# cpuofmicrocontroller.net
KiCad netlist of a schematic drawn in Altium Designer
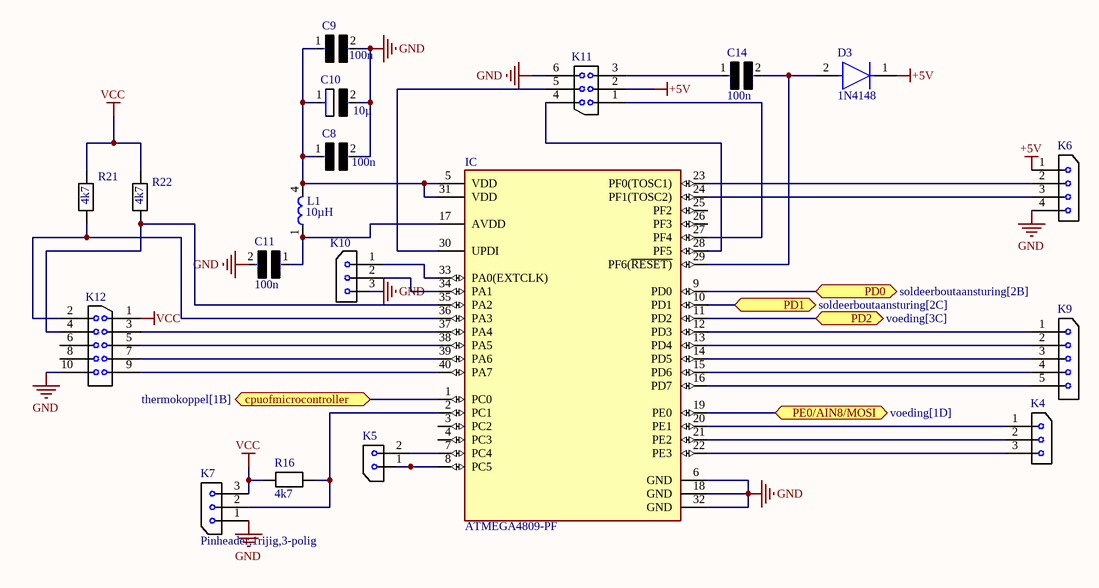
[diagram p0: cpuofmicrocontroller.SchDoc]

(export (version "E")
  (design (tool "Eeschema 10.0.6"))
  (components
    (comp (ref "C8")
      (value "100n")
      (footprint "RESC2013X50X30LL20T20")
      (libsource (lib "Schlib1") (part "capacitor2"))
    )
    (comp (ref "C9")
      (value "100n")
      (footprint "RESC2013X50X30LL20T20")
      (libsource (lib "Schlib1") (part "capacitor2"))
    )
    (comp (ref "C10")
      (value "10µ")
      (footprint "RESC2013X50X30LL20T20")
      (description "CAP CER 0.1UF 10V X5R 0402")
      (fields (field (name "MANUFACTURER") "Kemet") (field (name "TOLERANCE") "0.1"))
      (libsource (lib "Schlib1") (part "Capacitor"))
    )
    (comp (ref "C11")
      (value "100n")
      (footprint "RESC2013X50X30LL20T20")
      (libsource (lib "Schlib1") (part "capacitor2"))
    )
    (comp (ref "C14")
      (value "100n")
      (footprint "RESC2013X50X30LL20T20")
      (libsource (lib "Schlib1") (part "Ceramische Capacitor"))
    )
    (comp (ref "D3")
      (value "1N4148")
      (footprint "FP-017AG-MFG")
      (description "DIODE GEN PURP 100V 200MA DO35/1N4148")
      (fields (field (name "VOLTAGE") "100V"))
      (libsource (lib "Schlib1") (part "1N4148"))
    )
    (comp (ref "IC")
      (value "ATMEGA4809-PF")
      (footprint "FP-C04-016-MFG")
      (description "IC MCU 8BIT 48KB FLASH 40DIP")
      (libsource (lib "Schlib1") (part "aTmega4809-PF"))
    )
    (comp (ref "K4")
      (value "~")
      (footprint "PINHEADER, 1RIJIG,3-POLIG")
      (libsource (lib "Schlib1") (part "Pinheader,1rijig,3-polig"))
    )
    (comp (ref "K5")
      (value "~")
      (footprint "Pinheader,1rijig,2-polig")
      (libsource (lib "Schlib1") (part "Pinheader,1rijig,2-polig"))
    )
    (comp (ref "K6")
      (value "~")
      (footprint "PINHEADER, 1RIJIG,4-POLIG - duplicate")
      (libsource (lib "Schlib1") (part "Pinheader,1rijig,4-polig"))
    )
    (comp (ref "K7")
      (value "Pinheader,1rijig,3-polig")
      (footprint "PINHEADER, 1RIJIG,3-POLIG")
      (libsource (lib "Schlib1") (part "Pinheader,1rijig,3-polig"))
    )
    (comp (ref "K9")
      (value "~")
      (footprint "HDRV5W67P0X254_1X5_1270X241X858P")
      (description "Connector")
      (fields
        (field (name "MANUFACTURER_PART_NUMBER") "68000-105HTLF")
        (field (name "MOUSER PART NUMBER") "649-68000-105HTLF")
      )
      (libsource (lib "Schlib1") (part "5PIN HEADERmale"))
    )
    (comp (ref "K10")
      (value "~")
      (footprint "PINHEADER, 1RIJIG,3-POLIG")
      (libsource (lib "") (part "Pinheader,1rijig,3-polig_1"))
    )
    (comp (ref "K11")
      (value "~")
      (footprint "PINHEADER, 1RIJIG,6-POLIG - duplicate - duplicate")
      (libsource (lib "Schlib1") (part "Pinheader,2rijig,6-polig"))
    )
    (comp (ref "K12")
      (value "Pinheader,2rijig,10-polig")
      (footprint "PINHEADER, 2RIJIG,10-POLIG - duplicate - duplicate - duplicate")
      (libsource (lib "Schlib1") (part "Pinheader,2rijig,10-polig"))
    )
    (comp (ref "L1")
      (value "10µH")
      (footprint "Laird CM2545x171B-10")
      (libsource (lib "Schlib1") (part "spoelL1"))
    )
    (comp (ref "R16")
      (value "4k7")
      (footprint "RESC2013X50X30LL20T20")
      (fields (field (name "MANUFACTURER") "Vishay Dale") (field (name "PART NUMBER") "CRCW08050000Z0EA"))
      (libsource (lib "Schlib1") (part "weerstand"))
    )
    (comp (ref "R21")
      (value "4k7")
      (footprint "RESC2013X50X30LL20T20")
      (fields (field (name "MANUFACTURER") "Vishay Dale") (field (name "PART NUMBER") "CRCW08050000Z0EA"))
      (libsource (lib "Schlib1") (part "weerstand"))
    )
    (comp (ref "R22")
      (value "4k7")
      (footprint "RESC2013X50X30LL20T20")
      (fields (field (name "MANUFACTURER") "Vishay Dale") (field (name "PART NUMBER") "CRCW08050000Z0EA"))
      (libsource (lib "Schlib1") (part "weerstand"))
    )
  )
  (nets
    (net (code "1") (name "+5V") (class "Default")
      (node (ref "D3") (pin "1") (pinfunction "C_1") (pintype "passive"))
      (node (ref "K11") (pin "2") (pintype "passive"))
      (node (ref "K6") (pin "1") (pintype "passive"))
    )
    (net (code "2") (name "/PD0") (class "Default")
      (node (ref "IC") (pin "9") (pinfunction "PD0_9") (pintype "bidirectional"))
    )
    (net (code "3") (name "/PD1") (class "Default")
      (node (ref "IC") (pin "10") (pinfunction "PD1_10") (pintype "bidirectional"))
    )
    (net (code "4") (name "/PD2") (class "Default")
      (node (ref "IC") (pin "11") (pinfunction "PD2_11") (pintype "bidirectional"))
    )
    (net (code "5") (name "/PE0{slash}AIN8{slash}MOSI") (class "Default")
      (node (ref "IC") (pin "19") (pinfunction "PE0_19") (pintype "bidirectional"))
    )
    (net (code "6") (name "/cpuofmicrocontroller") (class "Default")
      (node (ref "IC") (pin "1") (pinfunction "PC0_1") (pintype "bidirectional"))
    )
    (net (code "7") (name "GND") (class "Default")
      (node (ref "C10") (pin "2") (pinfunction "2_2") (pintype "passive"))
      (node (ref "C11") (pin "2") (pinfunction "2_2") (pintype "passive"))
      (node (ref "C8") (pin "2") (pinfunction "2_2") (pintype "passive"))
      (node (ref "C9") (pin "2") (pinfunction "2_2") (pintype "passive"))
      (node (ref "IC") (pin "18") (pinfunction "GND_18") (pintype "power_in"))
      (node (ref "IC") (pin "32") (pinfunction "GND_32") (pintype "power_in"))
      (node (ref "IC") (pin "6") (pinfunction "GND_6") (pintype "power_in"))
      (node (ref "K10") (pin "3") (pintype "passive"))
      (node (ref "K11") (pin "6") (pintype "passive"))
      (node (ref "K12") (pin "10") (pintype "passive"))
      (node (ref "K6") (pin "4") (pintype "passive"))
      (node (ref "K7") (pin "1") (pintype "passive"))
    )
    (net (code "8") (name "Net-(C10-Pad1)") (class "Default")
      (node (ref "C10") (pin "1") (pinfunction "1_1") (pintype "passive"))
      (node (ref "C8") (pin "1") (pinfunction "2_1") (pintype "passive"))
      (node (ref "C9") (pin "1") (pinfunction "2_1") (pintype "passive"))
      (node (ref "IC") (pin "31") (pinfunction "VDD_31") (pintype "power_in"))
      (node (ref "IC") (pin "5") (pinfunction "VDD_5") (pintype "power_in"))
      (node (ref "L1") (pin "4") (pintype "passive"))
    )
    (net (code "9") (name "Net-(C14-2-Pad1)") (class "Default")
      (node (ref "C14") (pin "1") (pinfunction "2_1") (pintype "passive"))
      (node (ref "K11") (pin "3") (pintype "passive"))
    )
    (net (code "10") (name "Net-(D3-A)") (class "Default")
      (node (ref "C14") (pin "2") (pinfunction "2_2") (pintype "passive"))
      (node (ref "D3") (pin "2") (pinfunction "A_2") (pintype "passive"))
      (node (ref "IC") (pin "29") (pinfunction "PF6(~{RESET)}_29") (pintype "bidirectional"))
    )
    (net (code "11") (name "Net-(IC-AVDD)") (class "Default")
      (node (ref "C11") (pin "1") (pinfunction "2_1") (pintype "passive"))
      (node (ref "IC") (pin "17") (pinfunction "AVDD_17") (pintype "power_in"))
      (node (ref "L1") (pin "1") (pintype "passive"))
    )
    (net (code "12") (name "Net-(IC-PA0(EXTCLK))") (class "Default")
      (node (ref "IC") (pin "33") (pinfunction "PA0(EXTCLK)_33") (pintype "bidirectional"))
      (node (ref "K10") (pin "1") (pintype "passive"))
    )
    (net (code "13") (name "Net-(IC-PA1)") (class "Default")
      (node (ref "IC") (pin "34") (pinfunction "PA1_34") (pintype "bidirectional"))
      (node (ref "K10") (pin "2") (pintype "passive"))
    )
    (net (code "14") (name "Net-(IC-PA2)") (class "Default")
      (node (ref "IC") (pin "35") (pinfunction "PA2_35") (pintype "bidirectional"))
      (node (ref "K12") (pin "4") (pintype "passive"))
      (node (ref "R22") (pin "1") (pinfunction "1_1") (pintype "passive"))
    )
    (net (code "15") (name "Net-(IC-PA3)") (class "Default")
      (node (ref "IC") (pin "36") (pinfunction "PA3_36") (pintype "bidirectional"))
      (node (ref "K12") (pin "2") (pintype "passive"))
      (node (ref "R21") (pin "1") (pinfunction "1_1") (pintype "passive"))
    )
    (net (code "16") (name "Net-(IC-PA4)") (class "Default")
      (node (ref "IC") (pin "37") (pinfunction "PA4_37") (pintype "bidirectional"))
      (node (ref "K12") (pin "3") (pintype "passive"))
    )
    (net (code "17") (name "Net-(IC-PA5)") (class "Default")
      (node (ref "IC") (pin "38") (pinfunction "PA5_38") (pintype "bidirectional"))
      (node (ref "K12") (pin "5") (pintype "passive"))
    )
    (net (code "18") (name "Net-(IC-PA6)") (class "Default")
      (node (ref "IC") (pin "39") (pinfunction "PA6_39") (pintype "bidirectional"))
      (node (ref "K12") (pin "7") (pintype "passive"))
    )
    (net (code "19") (name "Net-(IC-PA7)") (class "Default")
      (node (ref "IC") (pin "40") (pinfunction "PA7_40") (pintype "bidirectional"))
      (node (ref "K12") (pin "9") (pintype "passive"))
    )
    (net (code "20") (name "Net-(IC-PC1)") (class "Default")
      (node (ref "IC") (pin "2") (pinfunction "PC1_2") (pintype "bidirectional"))
      (node (ref "K7") (pin "2") (pintype "passive"))
      (node (ref "R16") (pin "2") (pinfunction "2_2") (pintype "passive"))
    )
    (net (code "21") (name "Net-(IC-PC4)") (class "Default")
      (node (ref "IC") (pin "7") (pinfunction "PC4_7") (pintype "bidirectional"))
      (node (ref "K5") (pin "2") (pintype "passive"))
    )
    (net (code "22") (name "Net-(IC-PC5)") (class "Default")
      (node (ref "IC") (pin "8") (pinfunction "PC5_8") (pintype "bidirectional"))
      (node (ref "K5") (pin "1") (pintype "passive"))
    )
    (net (code "23") (name "Net-(IC-PD3)") (class "Default")
      (node (ref "IC") (pin "12") (pinfunction "PD3_12") (pintype "bidirectional"))
      (node (ref "K9") (pin "1") (pintype "passive"))
    )
    (net (code "24") (name "Net-(IC-PD4)") (class "Default")
      (node (ref "IC") (pin "13") (pinfunction "PD4_13") (pintype "bidirectional"))
      (node (ref "K9") (pin "2") (pintype "passive"))
    )
    (net (code "25") (name "Net-(IC-PD5)") (class "Default")
      (node (ref "IC") (pin "14") (pinfunction "PD5_14") (pintype "bidirectional"))
      (node (ref "K9") (pin "3") (pintype "passive"))
    )
    (net (code "26") (name "Net-(IC-PD6)") (class "Default")
      (node (ref "IC") (pin "15") (pinfunction "PD6_15") (pintype "bidirectional"))
      (node (ref "K9") (pin "4") (pintype "passive"))
    )
    (net (code "27") (name "Net-(IC-PD7)") (class "Default")
      (node (ref "IC") (pin "16") (pinfunction "PD7_16") (pintype "bidirectional"))
      (node (ref "K9") (pin "5") (pintype "passive"))
    )
    (net (code "28") (name "Net-(IC-PE1)") (class "Default")
      (node (ref "IC") (pin "20") (pinfunction "PE1_20") (pintype "bidirectional"))
      (node (ref "K4") (pin "1") (pintype "passive"))
    )
    (net (code "29") (name "Net-(IC-PE2)") (class "Default")
      (node (ref "IC") (pin "21") (pinfunction "PE2_21") (pintype "bidirectional"))
      (node (ref "K4") (pin "2") (pintype "passive"))
    )
    (net (code "30") (name "Net-(IC-PE3)") (class "Default")
      (node (ref "IC") (pin "22") (pinfunction "PE3_22") (pintype "bidirectional"))
      (node (ref "K4") (pin "3") (pintype "passive"))
    )
    (net (code "31") (name "Net-(IC-PF0(TOSC1))") (class "Default")
      (node (ref "IC") (pin "23") (pinfunction "PF0(TOSC1)_23") (pintype "bidirectional"))
      (node (ref "K6") (pin "2") (pintype "passive"))
    )
    (net (code "32") (name "Net-(IC-PF1(TOSC2))") (class "Default")
      (node (ref "IC") (pin "24") (pinfunction "PF1(TOSC2)_24") (pintype "bidirectional"))
      (node (ref "K6") (pin "3") (pintype "passive"))
    )
    (net (code "33") (name "Net-(IC-PF4)") (class "Default")
      (node (ref "IC") (pin "27") (pinfunction "PF4_27") (pintype "bidirectional"))
      (node (ref "K11") (pin "1") (pintype "passive"))
    )
    (net (code "34") (name "Net-(IC-PF5)") (class "Default")
      (node (ref "IC") (pin "28") (pinfunction "PF5_28") (pintype "bidirectional"))
      (node (ref "K11") (pin "4") (pintype "passive"))
    )
    (net (code "35") (name "Net-(IC-UPDI)") (class "Default")
      (node (ref "IC") (pin "30") (pinfunction "UPDI_30") (pintype "passive"))
      (node (ref "K11") (pin "5") (pintype "passive"))
    )
    (net (code "36") (name "VCC") (class "Default")
      (node (ref "K12") (pin "1") (pintype "passive"))
      (node (ref "K7") (pin "3") (pintype "passive"))
      (node (ref "R16") (pin "1") (pinfunction "1_1") (pintype "passive"))
      (node (ref "R21") (pin "2") (pinfunction "2_2") (pintype "passive"))
      (node (ref "R22") (pin "2") (pinfunction "2_2") (pintype "passive"))
    )
    (net (code "37") (name "unconnected-(IC-PC2-Pad3)") (class "Default")
      (node (ref "IC") (pin "3") (pinfunction "PC2_3") (pintype "bidirectional"))
    )
    (net (code "38") (name "unconnected-(IC-PC3-Pad4)") (class "Default")
      (node (ref "IC") (pin "4") (pinfunction "PC3_4") (pintype "bidirectional"))
    )
    (net (code "39") (name "unconnected-(IC-PF2-Pad25)") (class "Default")
      (node (ref "IC") (pin "25") (pinfunction "PF2_25") (pintype "bidirectional"))
    )
    (net (code "40") (name "unconnected-(IC-PF3-Pad26)") (class "Default")
      (node (ref "IC") (pin "26") (pinfunction "PF3_26") (pintype "bidirectional"))
    )
    (net (code "41") (name "unconnected-(K12-Pad6)") (class "Default")
      (node (ref "K12") (pin "6") (pintype "passive"))
    )
    (net (code "42") (name "unconnected-(K12-Pad8)") (class "Default")
      (node (ref "K12") (pin "8") (pintype "passive"))
    )
  )
)
